# POWER_1_2.net
KiCad netlist of a schematic drawn in Altium Designer
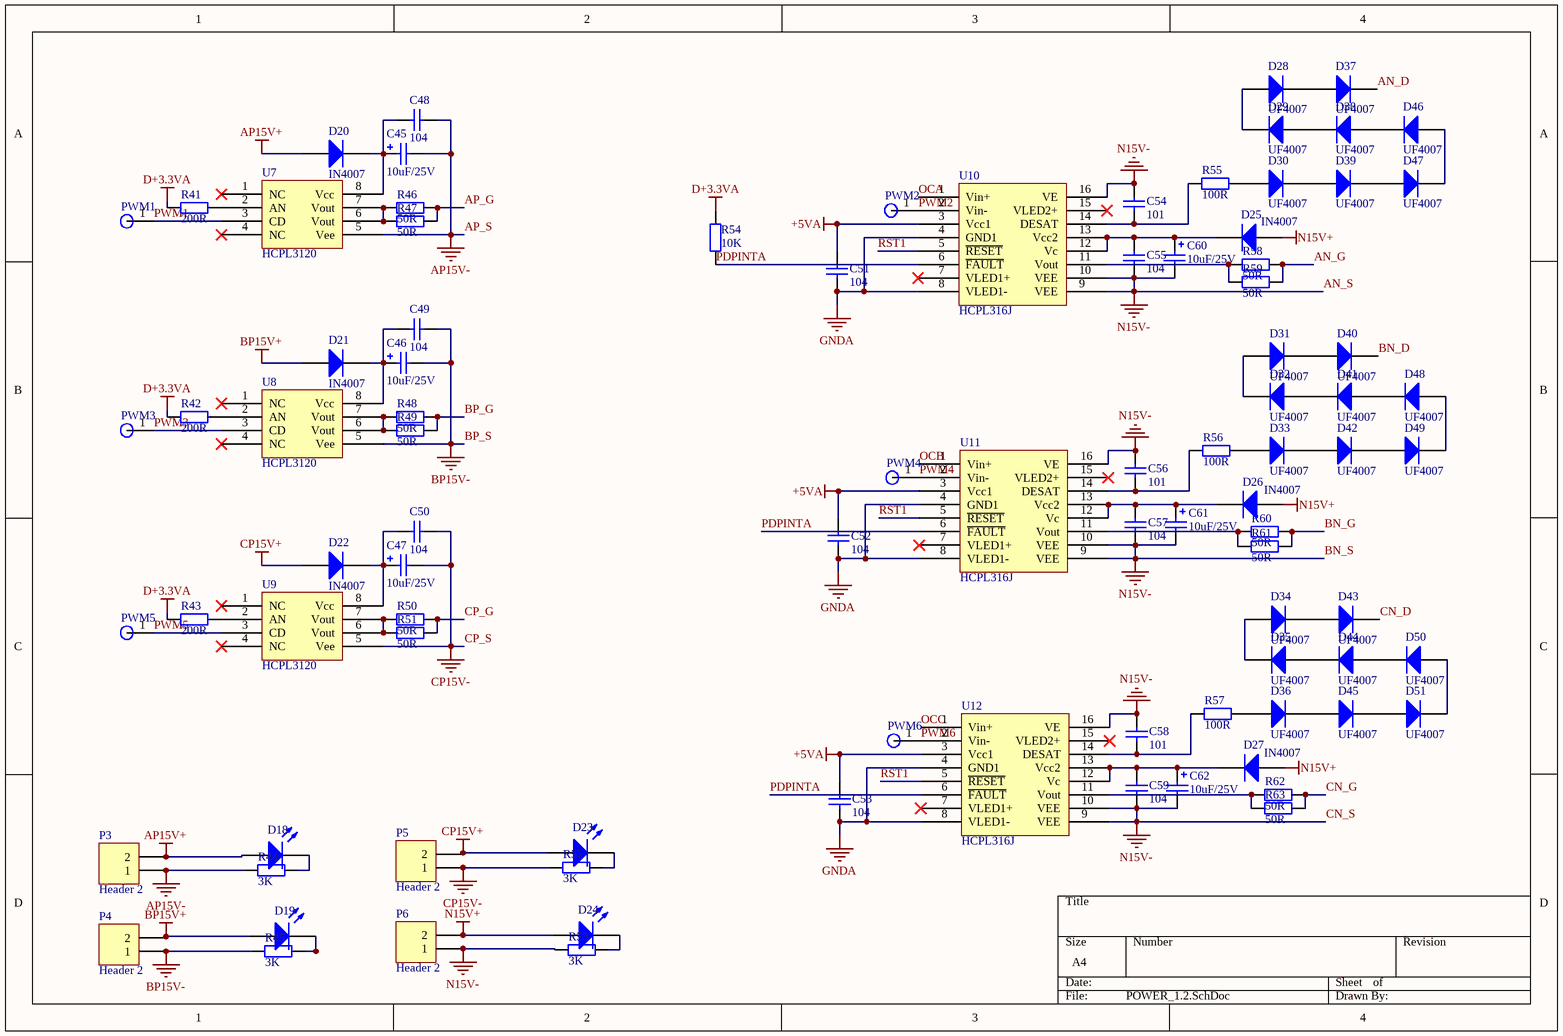
[diagram p0: POWER_1.2.SchDoc]

(export (version "E")
  (design (tool "Eeschema 10.0.6"))
  (components
    (comp (ref "C45")
      (value "10uF/25V")
      (footprint "C_10UF/25V")
      (description "钽电解")
      (libsource (lib "*") (part "Cap tan"))
    )
    (comp (ref "C46")
      (value "10uF/25V")
      (footprint "C_10UF/25V")
      (description "钽电解")
      (libsource (lib "*") (part "Cap tan"))
    )
    (comp (ref "C47")
      (value "10uF/25V")
      (footprint "C_10UF/25V")
      (description "钽电解")
      (libsource (lib "*") (part "Cap tan"))
    )
    (comp (ref "C48")
      (value "104")
      (footprint "C2012-0805")
      (description "普通电容")
      (libsource (lib "Mylib") (part "Cap"))
    )
    (comp (ref "C49")
      (value "104")
      (footprint "C2012-0805")
      (description "普通电容")
      (libsource (lib "Mylib") (part "Cap"))
    )
    (comp (ref "C50")
      (value "104")
      (footprint "C2012-0805")
      (description "普通电容")
      (libsource (lib "Mylib") (part "Cap"))
    )
    (comp (ref "C51")
      (value "104")
      (footprint "C2012-0805")
      (description "普通电容")
      (libsource (lib "*") (part "Cap"))
    )
    (comp (ref "C52")
      (value "104")
      (footprint "C2012-0805")
      (description "普通电容")
      (libsource (lib "*") (part "Cap"))
    )
    (comp (ref "C53")
      (value "104")
      (footprint "C2012-0805")
      (description "普通电容")
      (libsource (lib "*") (part "Cap"))
    )
    (comp (ref "C54")
      (value "101")
      (footprint "Rad-0.2")
      (description "普通电容")
      (libsource (lib "*") (part "Cap"))
    )
    (comp (ref "C55")
      (value "104")
      (footprint "C2012-0805")
      (description "普通电容")
      (libsource (lib "*") (part "Cap"))
    )
    (comp (ref "C56")
      (value "101")
      (footprint "Rad-0.2")
      (description "普通电容")
      (libsource (lib "*") (part "Cap"))
    )
    (comp (ref "C57")
      (value "104")
      (footprint "C2012-0805")
      (description "普通电容")
      (libsource (lib "*") (part "Cap"))
    )
    (comp (ref "C58")
      (value "101")
      (footprint "Rad-0.2")
      (description "普通电容")
      (libsource (lib "*") (part "Cap"))
    )
    (comp (ref "C59")
      (value "104")
      (footprint "C2012-0805")
      (description "普通电容")
      (libsource (lib "*") (part "Cap"))
    )
    (comp (ref "C60")
      (value "10uF/25V")
      (footprint "C_10UF/25V")
      (description "钽电解")
      (libsource (lib "*") (part "Cap tan"))
    )
    (comp (ref "C61")
      (value "10uF/25V")
      (footprint "C_10UF/25V")
      (description "钽电解")
      (libsource (lib "*") (part "Cap tan"))
    )
    (comp (ref "C62")
      (value "10uF/25V")
      (footprint "C_10UF/25V")
      (description "钽电解")
      (libsource (lib "*") (part "Cap tan"))
    )
    (comp (ref "D18") (value "~") (footprint "LED-SMD") (libsource (lib "Mylib") (part "LED")))
    (comp (ref "D19") (value "~") (footprint "LED-SMD") (libsource (lib "Mylib") (part "LED")))
    (comp (ref "D20")
      (value "IN4007")
      (footprint "DIODE4007")
      (description "普通整流二极管")
      (libsource (lib "Mylib") (part "Diode IN4007"))
    )
    (comp (ref "D21")
      (value "IN4007")
      (footprint "DIODE4007")
      (description "普通整流二极管")
      (libsource (lib "Mylib") (part "Diode IN4007"))
    )
    (comp (ref "D22")
      (value "IN4007")
      (footprint "DIODE4007")
      (description "普通整流二极管")
      (libsource (lib "Mylib") (part "Diode IN4007"))
    )
    (comp (ref "D23") (value "~") (footprint "LED-SMD") (libsource (lib "Mylib") (part "LED")))
    (comp (ref "D24") (value "~") (footprint "LED-SMD") (libsource (lib "Mylib") (part "LED")))
    (comp (ref "D25")
      (value "IN4007")
      (footprint "DIODE4007")
      (description "普通整流二极管")
      (libsource (lib "*") (part "Diode IN4007"))
    )
    (comp (ref "D26")
      (value "IN4007")
      (footprint "DIODE4007")
      (description "普通整流二极管")
      (libsource (lib "*") (part "Diode IN4007"))
    )
    (comp (ref "D27")
      (value "IN4007")
      (footprint "DIODE4007")
      (description "普通整流二极管")
      (libsource (lib "*") (part "Diode IN4007"))
    )
    (comp (ref "D28")
      (value "UF4007")
      (footprint "DIODE4007")
      (description "普通整流二极管")
      (libsource (lib "*") (part "Diode IN4007"))
    )
    (comp (ref "D29")
      (value "UF4007")
      (footprint "DIODE4007")
      (description "普通整流二极管")
      (libsource (lib "*") (part "Diode IN4007"))
    )
    (comp (ref "D30")
      (value "UF4007")
      (footprint "DIODE4007")
      (description "普通整流二极管")
      (libsource (lib "*") (part "Diode IN4007"))
    )
    (comp (ref "D31")
      (value "UF4007")
      (footprint "DIODE4007")
      (description "普通整流二极管")
      (libsource (lib "*") (part "Diode IN4007"))
    )
    (comp (ref "D32")
      (value "UF4007")
      (footprint "DIODE4007")
      (description "普通整流二极管")
      (libsource (lib "*") (part "Diode IN4007"))
    )
    (comp (ref "D33")
      (value "UF4007")
      (footprint "DIODE4007")
      (description "普通整流二极管")
      (libsource (lib "*") (part "Diode IN4007"))
    )
    (comp (ref "D34")
      (value "UF4007")
      (footprint "DIODE4007")
      (description "普通整流二极管")
      (libsource (lib "*") (part "Diode IN4007"))
    )
    (comp (ref "D35")
      (value "UF4007")
      (footprint "DIODE4007")
      (description "普通整流二极管")
      (libsource (lib "*") (part "Diode IN4007"))
    )
    (comp (ref "D36")
      (value "UF4007")
      (footprint "DIODE4007")
      (description "普通整流二极管")
      (libsource (lib "*") (part "Diode IN4007"))
    )
    (comp (ref "D37")
      (value "UF4007")
      (footprint "DIODE4007")
      (description "普通整流二极管")
      (libsource (lib "*") (part "Diode IN4007"))
    )
    (comp (ref "D38")
      (value "UF4007")
      (footprint "DIODE4007")
      (description "普通整流二极管")
      (libsource (lib "*") (part "Diode IN4007"))
    )
    (comp (ref "D39")
      (value "UF4007")
      (footprint "DIODE4007")
      (description "普通整流二极管")
      (libsource (lib "*") (part "Diode IN4007"))
    )
    (comp (ref "D40")
      (value "UF4007")
      (footprint "DIODE4007")
      (description "普通整流二极管")
      (libsource (lib "*") (part "Diode IN4007"))
    )
    (comp (ref "D41")
      (value "UF4007")
      (footprint "DIODE4007")
      (description "普通整流二极管")
      (libsource (lib "*") (part "Diode IN4007"))
    )
    (comp (ref "D42")
      (value "UF4007")
      (footprint "DIODE4007")
      (description "普通整流二极管")
      (libsource (lib "*") (part "Diode IN4007"))
    )
    (comp (ref "D43")
      (value "UF4007")
      (footprint "DIODE4007")
      (description "普通整流二极管")
      (libsource (lib "*") (part "Diode IN4007"))
    )
    (comp (ref "D44")
      (value "UF4007")
      (footprint "DIODE4007")
      (description "普通整流二极管")
      (libsource (lib "*") (part "Diode IN4007"))
    )
    (comp (ref "D45")
      (value "UF4007")
      (footprint "DIODE4007")
      (description "普通整流二极管")
      (libsource (lib "*") (part "Diode IN4007"))
    )
    (comp (ref "D46")
      (value "UF4007")
      (footprint "DIODE4007")
      (description "普通整流二极管")
      (libsource (lib "*") (part "Diode IN4007"))
    )
    (comp (ref "D47")
      (value "UF4007")
      (footprint "DIODE4007")
      (description "普通整流二极管")
      (libsource (lib "*") (part "Diode IN4007"))
    )
    (comp (ref "D48")
      (value "UF4007")
      (footprint "DIODE4007")
      (description "普通整流二极管")
      (libsource (lib "*") (part "Diode IN4007"))
    )
    (comp (ref "D49")
      (value "UF4007")
      (footprint "DIODE4007")
      (description "普通整流二极管")
      (libsource (lib "*") (part "Diode IN4007"))
    )
    (comp (ref "D50")
      (value "UF4007")
      (footprint "DIODE4007")
      (description "普通整流二极管")
      (libsource (lib "*") (part "Diode IN4007"))
    )
    (comp (ref "D51")
      (value "UF4007")
      (footprint "DIODE4007")
      (description "普通整流二极管")
      (libsource (lib "*") (part "Diode IN4007"))
    )
    (comp (ref "P3")
      (value "Header 2")
      (footprint "HDR1X2")
      (description "Header, 2-Pin")
      (fields (field (name "PUBLISHER") "Altium Limited"))
      (libsource (lib "Miscellaneous Connectors") (part "Header 2"))
    )
    (comp (ref "P4")
      (value "Header 2")
      (footprint "HDR1X2")
      (description "Header, 2-Pin")
      (fields (field (name "PUBLISHER") "Altium Limited"))
      (libsource (lib "Miscellaneous Connectors") (part "Header 2"))
    )
    (comp (ref "P5")
      (value "Header 2")
      (footprint "HDR1X2")
      (description "Header, 2-Pin")
      (fields (field (name "PUBLISHER") "Altium Limited"))
      (libsource (lib "Miscellaneous Connectors") (part "Header 2"))
    )
    (comp (ref "P6")
      (value "Header 2")
      (footprint "HDR1X2")
      (description "Header, 2-Pin")
      (fields (field (name "PUBLISHER") "Altium Limited"))
      (libsource (lib "Miscellaneous Connectors") (part "Header 2"))
    )
    (comp (ref "R41") (value "200R") (footprint "R2012-0805") (libsource (lib "*") (part "Res")))
    (comp (ref "R42") (value "200R") (footprint "R2012-0805") (libsource (lib "*") (part "Res")))
    (comp (ref "R43") (value "200R") (footprint "R2012-0805") (libsource (lib "*") (part "Res")))
    (comp (ref "R44") (value "3K") (footprint "R2012-0805") (libsource (lib "") (part "Res_2")))
    (comp (ref "R45") (value "3K") (footprint "R2012-0805") (libsource (lib "") (part "Res_2")))
    (comp (ref "R46") (value "50R") (footprint "R2012-0805") (libsource (lib "*") (part "Res")))
    (comp (ref "R47") (value "50R") (footprint "R2012-0805") (libsource (lib "*") (part "Res")))
    (comp (ref "R48") (value "50R") (footprint "R2012-0805") (libsource (lib "*") (part "Res")))
    (comp (ref "R49") (value "50R") (footprint "R2012-0805") (libsource (lib "*") (part "Res")))
    (comp (ref "R50") (value "50R") (footprint "R2012-0805") (libsource (lib "*") (part "Res")))
    (comp (ref "R51") (value "50R") (footprint "R2012-0805") (libsource (lib "*") (part "Res")))
    (comp (ref "R52") (value "3K") (footprint "R2012-0805") (libsource (lib "") (part "Res_2")))
    (comp (ref "R53") (value "3K") (footprint "R2012-0805") (libsource (lib "") (part "Res_2")))
    (comp (ref "R54") (value "10K") (footprint "R2012-0805") (libsource (lib "") (part "Res_1")))
    (comp (ref "R55") (value "100R") (footprint "R2012-0805") (libsource (lib "*") (part "Res")))
    (comp (ref "R56") (value "100R") (footprint "R2012-0805") (libsource (lib "*") (part "Res")))
    (comp (ref "R57") (value "100R") (footprint "R2012-0805") (libsource (lib "*") (part "Res")))
    (comp (ref "R58") (value "50R") (footprint "R2012-0805") (libsource (lib "*") (part "Res")))
    (comp (ref "R59") (value "50R") (footprint "R2012-0805") (libsource (lib "*") (part "Res")))
    (comp (ref "R60") (value "50R") (footprint "R2012-0805") (libsource (lib "*") (part "Res")))
    (comp (ref "R61") (value "50R") (footprint "R2012-0805") (libsource (lib "*") (part "Res")))
    (comp (ref "R62") (value "50R") (footprint "R2012-0805") (libsource (lib "*") (part "Res")))
    (comp (ref "R63") (value "50R") (footprint "R2012-0805") (libsource (lib "*") (part "Res")))
    (comp (ref "T16") (value "PWM2") (footprint "PIN1") (description "测试脚") (libsource (lib "*") (part "TP")))
    (comp (ref "T17") (value "PWM4") (footprint "PIN1") (description "测试脚") (libsource (lib "*") (part "TP")))
    (comp (ref "T18") (value "PWM6") (footprint "PIN1") (description "测试脚") (libsource (lib "*") (part "TP")))
    (comp (ref "TP2")
      (value "PWM1")
      (footprint "PIN1")
      (description "测试脚")
      (libsource (lib "Mylib") (part "TP"))
    )
    (comp (ref "TP3")
      (value "PWM3")
      (footprint "PIN1")
      (description "测试脚")
      (libsource (lib "Mylib") (part "TP"))
    )
    (comp (ref "TP4")
      (value "PWM5")
      (footprint "PIN1")
      (description "测试脚")
      (libsource (lib "Mylib") (part "TP"))
    )
    (comp (ref "U7") (value "HCPL3120") (footprint "HCPL3120") (libsource (lib "Mylib") (part "HCPL3120")))
    (comp (ref "U8") (value "HCPL3120") (footprint "HCPL3120") (libsource (lib "Mylib") (part "HCPL3120")))
    (comp (ref "U9") (value "HCPL3120") (footprint "HCPL3120") (libsource (lib "Mylib") (part "HCPL3120")))
    (comp (ref "U10") (value "HCPL316J") (footprint "HCPL316J") (libsource (lib "*") (part "HCPL316J")))
    (comp (ref "U11") (value "HCPL316J") (footprint "HCPL316J") (libsource (lib "*") (part "HCPL316J")))
    (comp (ref "U12") (value "HCPL316J") (footprint "HCPL316J") (libsource (lib "*") (part "HCPL316J")))
  )
  (nets
    (net (code "1") (name "+5VA") (class "Default")
      (node (ref "C51") (pin "2") (pinfunction "2_2") (pintype "passive"))
      (node (ref "C52") (pin "2") (pinfunction "2_2") (pintype "passive"))
      (node (ref "C53") (pin "2") (pinfunction "2_2") (pintype "passive"))
      (node (ref "U10") (pin "3") (pinfunction "Vcc1_3") (pintype "passive"))
      (node (ref "U11") (pin "3") (pinfunction "Vcc1_3") (pintype "passive"))
      (node (ref "U12") (pin "3") (pinfunction "Vcc1_3") (pintype "passive"))
    )
    (net (code "2") (name "/AN_D") (class "Default")
      (node (ref "D37") (pin "2") (pinfunction "K_2") (pintype "passive"))
    )
    (net (code "3") (name "/AN_G") (class "Default")
      (node (ref "R58") (pin "1") (pinfunction "1_1") (pintype "passive"))
      (node (ref "R59") (pin "1") (pinfunction "1_1") (pintype "passive"))
    )
    (net (code "4") (name "/AP_G") (class "Default")
      (node (ref "R46") (pin "1") (pinfunction "1_1") (pintype "passive"))
      (node (ref "R47") (pin "1") (pinfunction "1_1") (pintype "passive"))
    )
    (net (code "5") (name "/BN_D") (class "Default")
      (node (ref "D40") (pin "2") (pinfunction "K_2") (pintype "passive"))
    )
    (net (code "6") (name "/BN_G") (class "Default")
      (node (ref "R60") (pin "1") (pinfunction "1_1") (pintype "passive"))
      (node (ref "R61") (pin "1") (pinfunction "1_1") (pintype "passive"))
    )
    (net (code "7") (name "/BP_G") (class "Default")
      (node (ref "R48") (pin "1") (pinfunction "1_1") (pintype "passive"))
      (node (ref "R49") (pin "1") (pinfunction "1_1") (pintype "passive"))
    )
    (net (code "8") (name "/CN_D") (class "Default")
      (node (ref "D43") (pin "2") (pinfunction "K_2") (pintype "passive"))
    )
    (net (code "9") (name "/CN_G") (class "Default")
      (node (ref "R62") (pin "1") (pinfunction "1_1") (pintype "passive"))
      (node (ref "R63") (pin "1") (pinfunction "1_1") (pintype "passive"))
    )
    (net (code "10") (name "/CP_G") (class "Default")
      (node (ref "R50") (pin "1") (pinfunction "1_1") (pintype "passive"))
      (node (ref "R51") (pin "1") (pinfunction "1_1") (pintype "passive"))
    )
    (net (code "11") (name "/OCA") (class "Default")
      (node (ref "U10") (pin "1") (pinfunction "Vin+_1") (pintype "passive"))
    )
    (net (code "12") (name "/OCB") (class "Default")
      (node (ref "U11") (pin "1") (pinfunction "Vin+_1") (pintype "passive"))
    )
    (net (code "13") (name "/OCC") (class "Default")
      (node (ref "U12") (pin "1") (pinfunction "Vin+_1") (pintype "passive"))
    )
    (net (code "14") (name "/PDPINTA") (class "Default")
      (node (ref "R54") (pin "1") (pinfunction "1_1") (pintype "passive"))
      (node (ref "U10") (pin "6") (pinfunction "~{FAULT}_6") (pintype "passive"))
      (node (ref "U11") (pin "6") (pinfunction "~{FAULT}_6") (pintype "passive"))
      (node (ref "U12") (pin "6") (pinfunction "~{FAULT}_6") (pintype "passive"))
    )
    (net (code "15") (name "/PWM1") (class "Default")
      (node (ref "TP2") (pin "1") (pinfunction "A_1") (pintype "passive"))
      (node (ref "U7") (pin "3") (pinfunction "CD_3") (pintype "passive"))
    )
    (net (code "16") (name "/PWM2") (class "Default")
      (node (ref "T16") (pin "1") (pinfunction "A_1") (pintype "passive"))
      (node (ref "U10") (pin "2") (pinfunction "Vin-_2") (pintype "passive"))
    )
    (net (code "17") (name "/PWM3") (class "Default")
      (node (ref "TP3") (pin "1") (pinfunction "A_1") (pintype "passive"))
      (node (ref "U8") (pin "3") (pinfunction "CD_3") (pintype "passive"))
    )
    (net (code "18") (name "/PWM4") (class "Default")
      (node (ref "T17") (pin "1") (pinfunction "A_1") (pintype "passive"))
      (node (ref "U11") (pin "2") (pinfunction "Vin-_2") (pintype "passive"))
    )
    (net (code "19") (name "/PWM5") (class "Default")
      (node (ref "TP4") (pin "1") (pinfunction "A_1") (pintype "passive"))
      (node (ref "U9") (pin "3") (pinfunction "CD_3") (pintype "passive"))
    )
    (net (code "20") (name "/PWM6") (class "Default")
      (node (ref "T18") (pin "1") (pinfunction "A_1") (pintype "passive"))
      (node (ref "U12") (pin "2") (pinfunction "Vin-_2") (pintype "passive"))
    )
    (net (code "21") (name "/RST1") (class "Default")
      (node (ref "U10") (pin "5") (pinfunction "~{RESET}_5") (pintype "passive"))
      (node (ref "U11") (pin "5") (pinfunction "~{RESET}_5") (pintype "passive"))
      (node (ref "U12") (pin "5") (pinfunction "~{RESET}_5") (pintype "passive"))
    )
    (net (code "22") (name "AP15V+") (class "Default")
      (node (ref "D18") (pin "1") (pinfunction "A_1") (pintype "passive"))
      (node (ref "D20") (pin "1") (pinfunction "A_1") (pintype "passive"))
      (node (ref "P3") (pin "2") (pinfunction "2_2") (pintype "passive"))
    )
    (net (code "23") (name "AP15V-") (class "Default")
      (node (ref "C45") (pin "2") (pinfunction "2_2") (pintype "passive"))
      (node (ref "C48") (pin "2") (pinfunction "2_2") (pintype "passive"))
      (node (ref "P3") (pin "1") (pinfunction "1_1") (pintype "passive"))
      (node (ref "R44") (pin "1") (pinfunction "1_1") (pintype "passive"))
      (node (ref "U7") (pin "5") (pinfunction "Vee_5") (pintype "passive"))
    )
    (net (code "24") (name "BP15V+") (class "Default")
      (node (ref "D19") (pin "1") (pinfunction "A_1") (pintype "passive"))
      (node (ref "D21") (pin "1") (pinfunction "A_1") (pintype "passive"))
      (node (ref "P4") (pin "2") (pinfunction "2_2") (pintype "passive"))
    )
    (net (code "25") (name "BP15V-") (class "Default")
      (node (ref "C46") (pin "2") (pinfunction "2_2") (pintype "passive"))
      (node (ref "C49") (pin "2") (pinfunction "2_2") (pintype "passive"))
      (node (ref "P4") (pin "1") (pinfunction "1_1") (pintype "passive"))
      (node (ref "R45") (pin "1") (pinfunction "1_1") (pintype "passive"))
      (node (ref "U8") (pin "5") (pinfunction "Vee_5") (pintype "passive"))
    )
    (net (code "26") (name "CP15V+") (class "Default")
      (node (ref "D22") (pin "1") (pinfunction "A_1") (pintype "passive"))
      (node (ref "D23") (pin "1") (pinfunction "A_1") (pintype "passive"))
      (node (ref "P5") (pin "2") (pinfunction "2_2") (pintype "passive"))
    )
    (net (code "27") (name "CP15V-") (class "Default")
      (node (ref "C47") (pin "2") (pinfunction "2_2") (pintype "passive"))
      (node (ref "C50") (pin "2") (pinfunction "2_2") (pintype "passive"))
      (node (ref "P5") (pin "1") (pinfunction "1_1") (pintype "passive"))
      (node (ref "R52") (pin "1") (pinfunction "1_1") (pintype "passive"))
      (node (ref "U9") (pin "5") (pinfunction "Vee_5") (pintype "passive"))
    )
    (net (code "28") (name "D+3.3VA") (class "Default")
      (node (ref "R41") (pin "2") (pinfunction "2_2") (pintype "passive"))
      (node (ref "R42") (pin "2") (pinfunction "2_2") (pintype "passive"))
      (node (ref "R43") (pin "2") (pinfunction "2_2") (pintype "passive"))
      (node (ref "R54") (pin "2") (pinfunction "2_2") (pintype "passive"))
    )
    (net (code "29") (name "GNDA") (class "Default")
      (node (ref "C51") (pin "1") (pinfunction "1_1") (pintype "passive"))
      (node (ref "C52") (pin "1") (pinfunction "1_1") (pintype "passive"))
      (node (ref "C53") (pin "1") (pinfunction "1_1") (pintype "passive"))
      (node (ref "U10") (pin "4") (pinfunction "GND1_4") (pintype "passive"))
      (node (ref "U10") (pin "8") (pinfunction "VLED1-_8") (pintype "passive"))
      (node (ref "U11") (pin "4") (pinfunction "GND1_4") (pintype "passive"))
      (node (ref "U11") (pin "8") (pinfunction "VLED1-_8") (pintype "passive"))
      (node (ref "U12") (pin "4") (pinfunction "GND1_4") (pintype "passive"))
      (node (ref "U12") (pin "8") (pinfunction "VLED1-_8") (pintype "passive"))
    )
    (net (code "30") (name "N15V+") (class "Default")
      (node (ref "D24") (pin "1") (pinfunction "A_1") (pintype "passive"))
      (node (ref "D25") (pin "1") (pinfunction "A_1") (pintype "passive"))
      (node (ref "D26") (pin "1") (pinfunction "A_1") (pintype "passive"))
      (node (ref "D27") (pin "1") (pinfunction "A_1") (pintype "passive"))
      (node (ref "P6") (pin "2") (pinfunction "2_2") (pintype "passive"))
    )
    (net (code "31") (name "N15V-") (class "Default")
      (node (ref "C54") (pin "2") (pinfunction "2_2") (pintype "passive"))
      (node (ref "C55") (pin "1") (pinfunction "1_1") (pintype "passive"))
      (node (ref "C56") (pin "2") (pinfunction "2_2") (pintype "passive"))
      (node (ref "C57") (pin "1") (pinfunction "1_1") (pintype "passive"))
      (node (ref "C58") (pin "2") (pinfunction "2_2") (pintype "passive"))
      (node (ref "C59") (pin "1") (pinfunction "1_1") (pintype "passive"))
      (node (ref "C60") (pin "2") (pinfunction "2_2") (pintype "passive"))
      (node (ref "C61") (pin "2") (pinfunction "2_2") (pintype "passive"))
      (node (ref "C62") (pin "2") (pinfunction "2_2") (pintype "passive"))
      (node (ref "P6") (pin "1") (pinfunction "1_1") (pintype "passive"))
      (node (ref "R53") (pin "1") (pinfunction "1_1") (pintype "passive"))
      (node (ref "U10") (pin "10") (pinfunction "VEE_10") (pintype "passive"))
      (node (ref "U10") (pin "16") (pinfunction "VE_16") (pintype "passive"))
      (node (ref "U10") (pin "9") (pinfunction "VEE_9") (pintype "passive"))
      (node (ref "U11") (pin "10") (pinfunction "VEE_10") (pintype "passive"))
      (node (ref "U11") (pin "16") (pinfunction "VE_16") (pintype "passive"))
      (node (ref "U11") (pin "9") (pinfunction "VEE_9") (pintype "passive"))
      (node (ref "U12") (pin "10") (pinfunction "VEE_10") (pintype "passive"))
      (node (ref "U12") (pin "16") (pinfunction "VE_16") (pintype "passive"))
      (node (ref "U12") (pin "9") (pinfunction "VEE_9") (pintype "passive"))
    )
    (net (code "32") (name "Net-(D18-K)") (class "Default")
      (node (ref "D18") (pin "2") (pinfunction "K_2") (pintype "passive"))
      (node (ref "R44") (pin "2") (pinfunction "2_2") (pintype "passive"))
    )
    (net (code "33") (name "Net-(D19-K)") (class "Default")
      (node (ref "D19") (pin "2") (pinfunction "K_2") (pintype "passive"))
      (node (ref "R45") (pin "2") (pinfunction "2_2") (pintype "passive"))
    )
    (net (code "34") (name "Net-(D20-K)") (class "Default")
      (node (ref "C45") (pin "1") (pinfunction "1_1") (pintype "passive"))
      (node (ref "C48") (pin "1") (pinfunction "1_1") (pintype "passive"))
      (node (ref "D20") (pin "2") (pinfunction "K_2") (pintype "passive"))
      (node (ref "U7") (pin "8") (pinfunction "Vcc_8") (pintype "passive"))
    )
    (net (code "35") (name "Net-(D21-K)") (class "Default")
      (node (ref "C46") (pin "1") (pinfunction "1_1") (pintype "passive"))
      (node (ref "C49") (pin "1") (pinfunction "1_1") (pintype "passive"))
      (node (ref "D21") (pin "2") (pinfunction "K_2") (pintype "passive"))
      (node (ref "U8") (pin "8") (pinfunction "Vcc_8") (pintype "passive"))
    )
    (net (code "36") (name "Net-(D22-K)") (class "Default")
      (node (ref "C47") (pin "1") (pinfunction "1_1") (pintype "passive"))
      (node (ref "C50") (pin "1") (pinfunction "1_1") (pintype "passive"))
      (node (ref "D22") (pin "2") (pinfunction "K_2") (pintype "passive"))
      (node (ref "U9") (pin "8") (pinfunction "Vcc_8") (pintype "passive"))
    )
    (net (code "37") (name "Net-(D23-K)") (class "Default")
      (node (ref "D23") (pin "2") (pinfunction "K_2") (pintype "passive"))
      (node (ref "R52") (pin "2") (pinfunction "2_2") (pintype "passive"))
    )
    (net (code "38") (name "Net-(D24-K)") (class "Default")
      (node (ref "D24") (pin "2") (pinfunction "K_2") (pintype "passive"))
      (node (ref "R53") (pin "2") (pinfunction "2_2") (pintype "passive"))
    )
    (net (code "39") (name "Net-(D25-K)") (class "Default")
      (node (ref "C55") (pin "2") (pinfunction "2_2") (pintype "passive"))
      (node (ref "C60") (pin "1") (pinfunction "1_1") (pintype "passive"))
      (node (ref "D25") (pin "2") (pinfunction "K_2") (pintype "passive"))
      (node (ref "U10") (pin "12") (pinfunction "Vc_12") (pintype "passive"))
      (node (ref "U10") (pin "13") (pinfunction "Vcc2_13") (pintype "passive"))
    )
    (net (code "40") (name "Net-(D26-K)") (class "Default")
      (node (ref "C57") (pin "2") (pinfunction "2_2") (pintype "passive"))
      (node (ref "C61") (pin "1") (pinfunction "1_1") (pintype "passive"))
      (node (ref "D26") (pin "2") (pinfunction "K_2") (pintype "passive"))
      (node (ref "U11") (pin "12") (pinfunction "Vc_12") (pintype "passive"))
      (node (ref "U11") (pin "13") (pinfunction "Vcc2_13") (pintype "passive"))
    )
    (net (code "41") (name "Net-(D27-K)") (class "Default")
      (node (ref "C59") (pin "2") (pinfunction "2_2") (pintype "passive"))
      (node (ref "C62") (pin "1") (pinfunction "1_1") (pintype "passive"))
      (node (ref "D27") (pin "2") (pinfunction "K_2") (pintype "passive"))
      (node (ref "U12") (pin "12") (pinfunction "Vc_12") (pintype "passive"))
      (node (ref "U12") (pin "13") (pinfunction "Vcc2_13") (pintype "passive"))
    )
    (net (code "42") (name "Net-(D28-A)") (class "Default")
      (node (ref "D28") (pin "1") (pinfunction "A_1") (pintype "passive"))
      (node (ref "D29") (pin "2") (pinfunction "K_2") (pintype "passive"))
    )
    (net (code "43") (name "Net-(D28-K)") (class "Default")
      (node (ref "D28") (pin "2") (pinfunction "K_2") (pintype "passive"))
      (node (ref "D37") (pin "1") (pinfunction "A_1") (pintype "passive"))
    )
    (net (code "44") (name "Net-(D29-A)") (class "Default")
      (node (ref "D29") (pin "1") (pinfunction "A_1") (pintype "passive"))
      (node (ref "D38") (pin "2") (pinfunction "K_2") (pintype "passive"))
    )
    (net (code "45") (name "Net-(D30-A)") (class "Default")
      (node (ref "D30") (pin "1") (pinfunction "A_1") (pintype "passive"))
      (node (ref "R55") (pin "1") (pinfunction "1_1") (pintype "passive"))
    )
    (net (code "46") (name "Net-(D30-K)") (class "Default")
      (node (ref "D30") (pin "2") (pinfunction "K_2") (pintype "passive"))
      (node (ref "D39") (pin "1") (pinfunction "A_1") (pintype "passive"))
    )
    (net (code "47") (name "Net-(D31-A)") (class "Default")
      (node (ref "D31") (pin "1") (pinfunction "A_1") (pintype "passive"))
      (node (ref "D32") (pin "2") (pinfunction "K_2") (pintype "passive"))
    )
    (net (code "48") (name "Net-(D31-K)") (class "Default")
      (node (ref "D31") (pin "2") (pinfunction "K_2") (pintype "passive"))
      (node (ref "D40") (pin "1") (pinfunction "A_1") (pintype "passive"))
    )
    (net (code "49") (name "Net-(D32-A)") (class "Default")
      (node (ref "D32") (pin "1") (pinfunction "A_1") (pintype "passive"))
      (node (ref "D41") (pin "2") (pinfunction "K_2") (pintype "passive"))
    )
    (net (code "50") (name "Net-(D33-A)") (class "Default")
      (node (ref "D33") (pin "1") (pinfunction "A_1") (pintype "passive"))
      (node (ref "R56") (pin "1") (pinfunction "1_1") (pintype "passive"))
    )
    (net (code "51") (name "Net-(D33-K)") (class "Default")
      (node (ref "D33") (pin "2") (pinfunction "K_2") (pintype "passive"))
      (node (ref "D42") (pin "1") (pinfunction "A_1") (pintype "passive"))
    )
    (net (code "52") (name "Net-(D34-A)") (class "Default")
      (node (ref "D34") (pin "1") (pinfunction "A_1") (pintype "passive"))
      (node (ref "D35") (pin "2") (pinfunction "K_2") (pintype "passive"))
    )
    (net (code "53") (name "Net-(D34-K)") (class "Default")
      (node (ref "D34") (pin "2") (pinfunction "K_2") (pintype "passive"))
      (node (ref "D43") (pin "1") (pinfunction "A_1") (pintype "passive"))
    )
    (net (code "54") (name "Net-(D35-A)") (class "Default")
      (node (ref "D35") (pin "1") (pinfunction "A_1") (pintype "passive"))
      (node (ref "D44") (pin "2") (pinfunction "K_2") (pintype "passive"))
    )
    (net (code "55") (name "Net-(D36-A)") (class "Default")
      (node (ref "D36") (pin "1") (pinfunction "A_1") (pintype "passive"))
      (node (ref "R57") (pin "1") (pinfunction "1_1") (pintype "passive"))
    )
    (net (code "56") (name "Net-(D36-K)") (class "Default")
      (node (ref "D36") (pin "2") (pinfunction "K_2") (pintype "passive"))
      (node (ref "D45") (pin "1") (pinfunction "A_1") (pintype "passive"))
    )
    (net (code "57") (name "Net-(D38-A)") (class "Default")
      (node (ref "D38") (pin "1") (pinfunction "A_1") (pintype "passive"))
      (node (ref "D46") (pin "2") (pinfunction "K_2") (pintype "passive"))
    )
    (net (code "58") (name "Net-(D39-K)") (class "Default")
      (node (ref "D39") (pin "2") (pinfunction "K_2") (pintype "passive"))
      (node (ref "D47") (pin "1") (pinfunction "A_1") (pintype "passive"))
    )
    (net (code "59") (name "Net-(D41-A)") (class "Default")
      (node (ref "D41") (pin "1") (pinfunction "A_1") (pintype "passive"))
      (node (ref "D48") (pin "2") (pinfunction "K_2") (pintype "passive"))
    )
    (net (code "60") (name "Net-(D42-K)") (class "Default")
      (node (ref "D42") (pin "2") (pinfunction "K_2") (pintype "passive"))
      (node (ref "D49") (pin "1") (pinfunction "A_1") (pintype "passive"))
    )
    (net (code "61") (name "Net-(D44-A)") (class "Default")
      (node (ref "D44") (pin "1") (pinfunction "A_1") (pintype "passive"))
      (node (ref "D50") (pin "2") (pinfunction "K_2") (pintype "passive"))
    )
    (net (code "62") (name "Net-(D45-K)") (class "Default")
      (node (ref "D45") (pin "2") (pinfunction "K_2") (pintype "passive"))
      (node (ref "D51") (pin "1") (pinfunction "A_1") (pintype "passive"))
    )
    (net (code "63") (name "Net-(D46-A)") (class "Default")
      (node (ref "D46") (pin "1") (pinfunction "A_1") (pintype "passive"))
      (node (ref "D47") (pin "2") (pinfunction "K_2") (pintype "passive"))
    )
    (net (code "64") (name "Net-(D48-A)") (class "Default")
      (node (ref "D48") (pin "1") (pinfunction "A_1") (pintype "passive"))
      (node (ref "D49") (pin "2") (pinfunction "K_2") (pintype "passive"))
    )
    (net (code "65") (name "Net-(D50-A)") (class "Default")
      (node (ref "D50") (pin "1") (pinfunction "A_1") (pintype "passive"))
      (node (ref "D51") (pin "2") (pinfunction "K_2") (pintype "passive"))
    )
    (net (code "66") (name "Net-(R46-Pad2)") (class "Default")
      (node (ref "R46") (pin "2") (pinfunction "2_2") (pintype "passive"))
      (node (ref "R47") (pin "2") (pinfunction "2_2") (pintype "passive"))
      (node (ref "U7") (pin "6") (pinfunction "Vout_6") (pintype "passive"))
      (node (ref "U7") (pin "7") (pinfunction "Vout_7") (pintype "passive"))
    )
    (net (code "67") (name "Net-(R48-Pad2)") (class "Default")
      (node (ref "R48") (pin "2") (pinfunction "2_2") (pintype "passive"))
      (node (ref "R49") (pin "2") (pinfunction "2_2") (pintype "passive"))
      (node (ref "U8") (pin "6") (pinfunction "Vout_6") (pintype "passive"))
      (node (ref "U8") (pin "7") (pinfunction "Vout_7") (pintype "passive"))
    )
    (net (code "68") (name "Net-(R50-Pad2)") (class "Default")
      (node (ref "R50") (pin "2") (pinfunction "2_2") (pintype "passive"))
      (node (ref "R51") (pin "2") (pinfunction "2_2") (pintype "passive"))
      (node (ref "U9") (pin "6") (pinfunction "Vout_6") (pintype "passive"))
      (node (ref "U9") (pin "7") (pinfunction "Vout_7") (pintype "passive"))
    )
    (net (code "69") (name "Net-(U7-AN)") (class "Default")
      (node (ref "R41") (pin "1") (pinfunction "1_1") (pintype "passive"))
      (node (ref "U7") (pin "2") (pinfunction "AN_2") (pintype "passive"))
    )
    (net (code "70") (name "Net-(U8-AN)") (class "Default")
      (node (ref "R42") (pin "1") (pinfunction "1_1") (pintype "passive"))
      (node (ref "U8") (pin "2") (pinfunction "AN_2") (pintype "passive"))
    )
    (net (code "71") (name "Net-(U9-AN)") (class "Default")
      (node (ref "R43") (pin "1") (pinfunction "1_1") (pintype "passive"))
      (node (ref "U9") (pin "2") (pinfunction "AN_2") (pintype "passive"))
    )
    (net (code "72") (name "Net-(U10-DESAT)") (class "Default")
      (node (ref "C54") (pin "1") (pinfunction "1_1") (pintype "passive"))
      (node (ref "R55") (pin "2") (pinfunction "2_2") (pintype "passive"))
      (node (ref "U10") (pin "14") (pinfunction "DESAT_14") (pintype "passive"))
    )
    (net (code "73") (name "Net-(U10-Vout)") (class "Default")
      (node (ref "R58") (pin "2") (pinfunction "2_2") (pintype "passive"))
      (node (ref "R59") (pin "2") (pinfunction "2_2") (pintype "passive"))
      (node (ref "U10") (pin "11") (pinfunction "Vout_11") (pintype "passive"))
    )
    (net (code "74") (name "Net-(U11-DESAT)") (class "Default")
      (node (ref "C56") (pin "1") (pinfunction "1_1") (pintype "passive"))
      (node (ref "R56") (pin "2") (pinfunction "2_2") (pintype "passive"))
      (node (ref "U11") (pin "14") (pinfunction "DESAT_14") (pintype "passive"))
    )
    (net (code "75") (name "Net-(U11-Vout)") (class "Default")
      (node (ref "R60") (pin "2") (pinfunction "2_2") (pintype "passive"))
      (node (ref "R61") (pin "2") (pinfunction "2_2") (pintype "passive"))
      (node (ref "U11") (pin "11") (pinfunction "Vout_11") (pintype "passive"))
    )
    (net (code "76") (name "Net-(U12-DESAT)") (class "Default")
      (node (ref "C58") (pin "1") (pinfunction "1_1") (pintype "passive"))
      (node (ref "R57") (pin "2") (pinfunction "2_2") (pintype "passive"))
      (node (ref "U12") (pin "14") (pinfunction "DESAT_14") (pintype "passive"))
    )
    (net (code "77") (name "Net-(U12-Vout)") (class "Default")
      (node (ref "R62") (pin "2") (pinfunction "2_2") (pintype "passive"))
      (node (ref "R63") (pin "2") (pinfunction "2_2") (pintype "passive"))
      (node (ref "U12") (pin "11") (pinfunction "Vout_11") (pintype "passive"))
    )
    (net (code "78") (name "unconnected-(U7-NC-Pad1)") (class "Default")
      (node (ref "U7") (pin "1") (pinfunction "NC_1") (pintype "passive+no_connect"))
    )
    (net (code "79") (name "unconnected-(U7-NC-Pad4)") (class "Default")
      (node (ref "U7") (pin "4") (pinfunction "NC_4") (pintype "passive+no_connect"))
    )
    (net (code "80") (name "unconnected-(U8-NC-Pad1)") (class "Default")
      (node (ref "U8") (pin "1") (pinfunction "NC_1") (pintype "passive+no_connect"))
    )
    (net (code "81") (name "unconnected-(U8-NC-Pad4)") (class "Default")
      (node (ref "U8") (pin "4") (pinfunction "NC_4") (pintype "passive+no_connect"))
    )
    (net (code "82") (name "unconnected-(U9-NC-Pad1)") (class "Default")
      (node (ref "U9") (pin "1") (pinfunction "NC_1") (pintype "passive+no_connect"))
    )
    (net (code "83") (name "unconnected-(U9-NC-Pad4)") (class "Default")
      (node (ref "U9") (pin "4") (pinfunction "NC_4") (pintype "passive+no_connect"))
    )
    (net (code "84") (name "unconnected-(U10-VLED1+-Pad7)") (class "Default")
      (node (ref "U10") (pin "7") (pinfunction "VLED1+_7") (pintype "passive+no_connect"))
    )
    (net (code "85") (name "unconnected-(U10-VLED2+-Pad15)") (class "Default")
      (node (ref "U10") (pin "15") (pinfunction "VLED2+_15") (pintype "passive+no_connect"))
    )
    (net (code "86") (name "unconnected-(U11-VLED1+-Pad7)") (class "Default")
      (node (ref "U11") (pin "7") (pinfunction "VLED1+_7") (pintype "passive+no_connect"))
    )
    (net (code "87") (name "unconnected-(U11-VLED2+-Pad15)") (class "Default")
      (node (ref "U11") (pin "15") (pinfunction "VLED2+_15") (pintype "passive+no_connect"))
    )
    (net (code "88") (name "unconnected-(U12-VLED1+-Pad7)") (class "Default")
      (node (ref "U12") (pin "7") (pinfunction "VLED1+_7") (pintype "passive+no_connect"))
    )
    (net (code "89") (name "unconnected-(U12-VLED2+-Pad15)") (class "Default")
      (node (ref "U12") (pin "15") (pinfunction "VLED2+_15") (pintype "passive+no_connect"))
    )
  )
)
